# 003_Debugging.net
KiCad netlist of a schematic drawn in Altium Designer
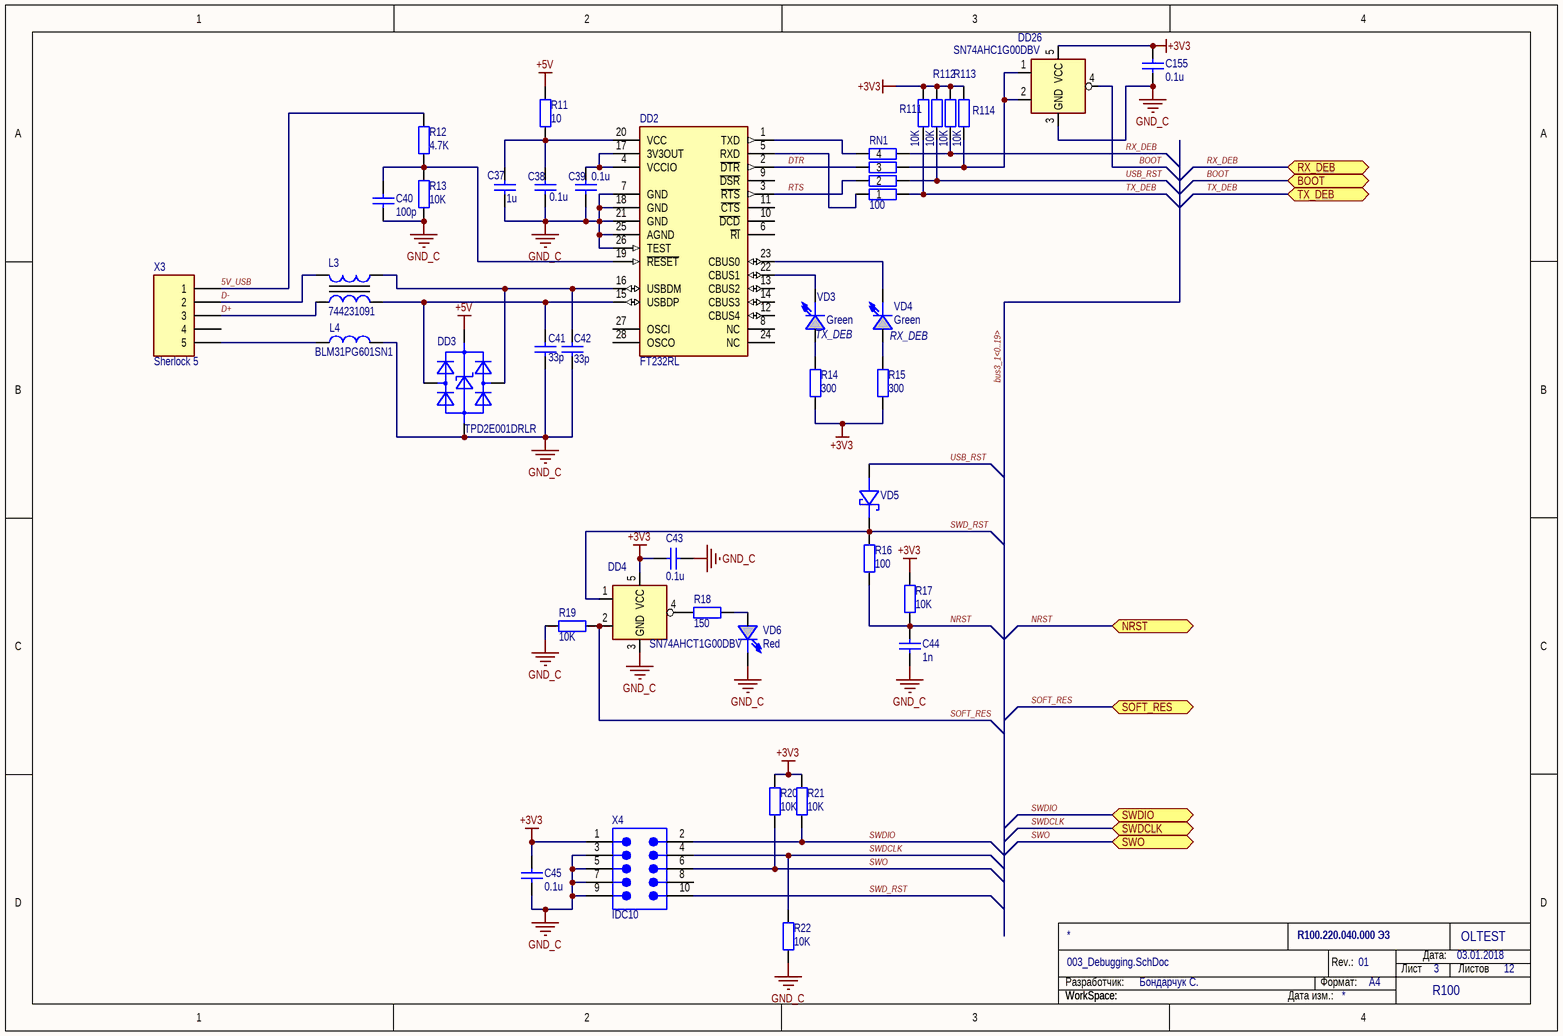
[diagram p0: 003_Debugging.SchDoc]

(export (version "E")
  (design (tool "Eeschema 10.0.6"))
  (components
    (comp (ref "C37")
      (value "1u")
      (footprint "mainLib:SMD_C_0603")
      (description "SMD C 0603 MURATA 25V 10% X7R")
      (fields (field (name "PARTNUMBER") "GRM188R71E105KA12") (field (name "MANUFACTURER") "MURATA"))
      (libsource (lib "mainRCLib") (part "C0603 1uF 25V 10%"))
    )
    (comp (ref "C38")
      (value "0.1u")
      (footprint "mainLib:SMD_C_0603")
      (description "SMD C 0603 MURATA 50V 10% X7R")
      (fields (field (name "PARTNUMBER") "GRM188R71H104K") (field (name "MANUFACTURER") "MURATA"))
      (libsource (lib "mainRCLib") (part "C0603 0.1u 50V 10%"))
    )
    (comp (ref "C39")
      (value "0.1u")
      (footprint "mainLib:SMD_C_0603")
      (description "SMD C 0603 MURATA 50V 10% X7R")
      (fields (field (name "PARTNUMBER") "GRM188R71H104K") (field (name "MANUFACTURER") "MURATA"))
      (libsource (lib "mainRCLib") (part "C0603 0.1u 50V 10%"))
    )
    (comp (ref "C40")
      (value "100p")
      (footprint "mainLib:SMD_C_0603")
      (description "SMD C 0603 MURATA 100V 5% NP0")
      (fields (field (name "PARTNUMBER") "GRM1885C2A101JA01") (field (name "MANUFACTURER") "MURATA"))
      (libsource (lib "mainRCLib") (part "C0603 100p 100V 5%"))
    )
    (comp (ref "C41")
      (value "33p")
      (footprint "mainLib:SMD_C_0603")
      (description "SMD C 0603 MURATA 50V 5% NP0")
      (fields (field (name "PARTNUMBER") "GRM1885C1H330JA01") (field (name "MANUFACTURER") "MURATA"))
      (libsource (lib "mainRCLib") (part "C0603 33p 50V 5%"))
    )
    (comp (ref "C42")
      (value "33p")
      (footprint "mainLib:SMD_C_0603")
      (description "SMD C 0603 MURATA 50V 5% NP0")
      (fields (field (name "PARTNUMBER") "GRM1885C1H330JA01") (field (name "MANUFACTURER") "MURATA"))
      (libsource (lib "mainRCLib") (part "C0603 33p 50V 5%"))
    )
    (comp (ref "C43")
      (value "0.1u")
      (footprint "mainLib:SMD_C_0603")
      (description "SMD C 0603 MURATA 50V 10% X7R")
      (fields (field (name "PARTNUMBER") "GRM188R71H104K") (field (name "MANUFACTURER") "MURATA"))
      (libsource (lib "mainRCLib") (part "C0603 0.1u 50V 10%"))
    )
    (comp (ref "C44")
      (value "1n")
      (footprint "mainLib:SMD_C_0603")
      (description "SMD C 0603 MURATA 50V 5% NP0")
      (fields (field (name "PARTNUMBER") "GRM1885C1H102JA01") (field (name "MANUFACTURER") "MURATA"))
      (libsource (lib "mainRCLib") (part "C0603 1n 50V 5%"))
    )
    (comp (ref "C45")
      (value "0.1u")
      (footprint "mainLib:SMD_C_0603")
      (description "SMD C 0603 MURATA 50V 10% X7R")
      (fields (field (name "PARTNUMBER") "GRM188R71H104K") (field (name "MANUFACTURER") "MURATA"))
      (libsource (lib "mainRCLib") (part "C0603 0.1u 50V 10%"))
    )
    (comp (ref "C155")
      (value "0.1u")
      (footprint "mainLib:SMD_C_0603")
      (description "SMD C 0603 MURATA 50V 10% X7R")
      (fields (field (name "PARTNUMBER") "GRM188R71H104K") (field (name "MANUFACTURER") "MURATA"))
      (libsource (lib "mainRCLib") (part "C0603 0.1u 50V 10%"))
    )
    (comp (ref "DD2")
      (value "FT232RL")
      (footprint "mainLib:SSOP-28_M")
      (description "USB UART Asynchronous Serial Data Transfer Chip, 28-pin SSOP")
      (fields (field (name "MANUFACTURER") "FTDI"))
      (libsource (lib "mainLib") (part "FT232RL"))
    )
    (comp (ref "DD3")
      (value "TPD2E001DRLR")
      (footprint "mainLib:DRL5_M")
      (fields (field (name "MANUFACTURER") "Texas Instruments"))
      (libsource (lib "mainLib") (part "TPD2E001DRLR"))
    )
    (comp (ref "DD4")
      (value "SN74AHCT1G00DBV")
      (footprint "mainLib:SOT-23(DBV)")
      (description "2-in NAND")
      (fields (field (name "MANUFACTURER") "Texas Instruments"))
      (libsource (lib "mainLib") (part "SN74AHCT1G00DBV"))
    )
    (comp (ref "DD26")
      (value "SN74AHC1G00DBV")
      (footprint "mainLib:SOT-23(DBV)")
      (description "2-in NAND")
      (fields (field (name "MANUFACTURER") "Texas Instruments"))
      (libsource (lib "mainLib") (part "SN74AHC1G00DBV"))
    )
    (comp (ref "L3")
      (value "744231091")
      (footprint "mainLib:WE-CNSW-0805")
      (description "SMD Common Mode Noise Suppressor WE-CNSW, Z = 90 Ohm")
      (fields (field (name "MANUFACTURER") "Wurth Elektronik"))
      (libsource (lib "mainLib") (part "744231091"))
    )
    (comp (ref "L4")
      (value "BLM31PG601SN1")
      (footprint "mainLib:SMD_L_1206")
      (description "600R 1.5A (100MHz)")
      (fields (field (name "MANUFACTURER") "TDK") (field (name "PARTNUMBER") "BLM31PG601SN1"))
      (libsource (lib "mainLib") (part "BLM31PG601SN1"))
    )
    (comp (ref "R11")
      (value "10")
      (footprint "mainLib:SMD_R_0805")
      (description "SMD R 0805 VISHAY 0.125W 150V 1% 100ppm")
      (fields (field (name "PARTNUMBER") "CRCW080510R0FK") (field (name "MANUFACTURER") "VISHAY"))
      (libsource (lib "mainRCLib") (part "R0805 10 1%"))
    )
    (comp (ref "R12")
      (value "4.7K")
      (footprint "mainLib:SMD_R_0805")
      (description "SMD R 0805 VISHAY 0.125W 150V 1% 100ppm")
      (fields (field (name "PARTNUMBER") "CRCW08054K70FK") (field (name "MANUFACTURER") "VISHAY"))
      (libsource (lib "mainRCLib") (part "R0805 4.7K 1%"))
    )
    (comp (ref "R13")
      (value "10K")
      (footprint "mainLib:SMD_R_0805")
      (description "SMD R 0805 VISHAY 0.125W 150V 1% 100ppm")
      (fields (field (name "PARTNUMBER") "CRCW080510K0FK") (field (name "MANUFACTURER") "VISHAY"))
      (libsource (lib "mainRCLib") (part "R0805 10K 1%"))
    )
    (comp (ref "R14")
      (value "300")
      (footprint "mainLib:SMD_R_0805")
      (description "SMD R 0805 VISHAY 0.125W 150V 1% 100ppm")
      (fields (field (name "PARTNUMBER") "CRCW0805300RFK") (field (name "MANUFACTURER") "VISHAY"))
      (libsource (lib "mainRCLib") (part "R0805 300 1%"))
    )
    (comp (ref "R15")
      (value "300")
      (footprint "mainLib:SMD_R_0805")
      (description "SMD R 0805 VISHAY 0.125W 150V 1% 100ppm")
      (fields (field (name "PARTNUMBER") "CRCW0805300RFK") (field (name "MANUFACTURER") "VISHAY"))
      (libsource (lib "mainRCLib") (part "R0805 300 1%"))
    )
    (comp (ref "R16")
      (value "100")
      (footprint "SMD_R_0603")
      (description "SMD R 0603 VISHAY 0.1W 75V 1% 100ppm")
      (fields (field (name "PARTNUMBER") "CRCW0603100RFK") (field (name "MANUFACTURER") "VISHAY"))
      (libsource (lib "mainRCLib") (part "R0603 100 1%"))
    )
    (comp (ref "R17")
      (value "10K")
      (footprint "SMD_R_0603")
      (description "SMD R 0603 VISHAY 0.1W 75V 1% 100ppm")
      (fields (field (name "PARTNUMBER") "CRCW060310K0FK") (field (name "MANUFACTURER") "VISHAY"))
      (libsource (lib "mainRCLib") (part "R0603 10К 1%"))
    )
    (comp (ref "R18")
      (value "150")
      (footprint "mainLib:SMD_R_0805")
      (description "SMD 0805 VISHAY 0.125W 150V 1% 100ppm")
      (fields (field (name "PARTNUMBER") "CRCW0805150RFK") (field (name "MANUFACTURER") "VISHAY"))
      (libsource (lib "mainRCLib") (part "R0805 150 1%"))
    )
    (comp (ref "R19")
      (value "10K")
      (footprint "SMD_R_0603")
      (description "SMD R 0603 VISHAY 0.1W 75V 1% 100ppm")
      (fields (field (name "PARTNUMBER") "CRCW060310K0FK") (field (name "MANUFACTURER") "VISHAY"))
      (libsource (lib "") (part "R0603 10К 1%_1"))
    )
    (comp (ref "R20")
      (value "10K")
      (footprint "SMD_R_0603")
      (description "SMD R 0603 VISHAY 0.1W 75V 1% 100ppm")
      (fields (field (name "PARTNUMBER") "CRCW060310K0FK") (field (name "MANUFACTURER") "VISHAY"))
      (libsource (lib "mainRCLib") (part "R0603 10К 1%"))
    )
    (comp (ref "R21")
      (value "10K")
      (footprint "SMD_R_0603")
      (description "SMD R 0603 VISHAY 0.1W 75V 1% 100ppm")
      (fields (field (name "PARTNUMBER") "CRCW060310K0FK") (field (name "MANUFACTURER") "VISHAY"))
      (libsource (lib "mainRCLib") (part "R0603 10К 1%"))
    )
    (comp (ref "R22")
      (value "10K")
      (footprint "SMD_R_0603")
      (description "SMD R 0603 VISHAY 0.1W 75V 1% 100ppm")
      (fields (field (name "PARTNUMBER") "CRCW060310K0FK") (field (name "MANUFACTURER") "VISHAY"))
      (libsource (lib "mainRCLib") (part "R0603 10К 1%"))
    )
    (comp (ref "R111")
      (value "10K")
      (footprint "SMD_R_0603")
      (description "SMD R 0603 VISHAY 0.1W 75V 1% 100ppm")
      (fields (field (name "PARTNUMBER") "CRCW060310K0FK") (field (name "MANUFACTURER") "VISHAY"))
      (libsource (lib "mainRCLib") (part "R0603 10К 1%"))
    )
    (comp (ref "R112")
      (value "10K")
      (footprint "SMD_R_0603")
      (description "SMD R 0603 VISHAY 0.1W 75V 1% 100ppm")
      (fields (field (name "PARTNUMBER") "CRCW060310K0FK") (field (name "MANUFACTURER") "VISHAY"))
      (libsource (lib "mainRCLib") (part "R0603 10К 1%"))
    )
    (comp (ref "R113")
      (value "10K")
      (footprint "SMD_R_0603")
      (description "SMD R 0603 VISHAY 0.1W 75V 1% 100ppm")
      (fields (field (name "PARTNUMBER") "CRCW060310K0FK") (field (name "MANUFACTURER") "VISHAY"))
      (libsource (lib "mainRCLib") (part "R0603 10К 1%"))
    )
    (comp (ref "R114")
      (value "10K")
      (footprint "SMD_R_0603")
      (description "SMD R 0603 VISHAY 0.1W 75V 1% 100ppm")
      (fields (field (name "PARTNUMBER") "CRCW060310K0FK") (field (name "MANUFACTURER") "VISHAY"))
      (libsource (lib "mainRCLib") (part "R0603 10К 1%"))
    )
    (comp (ref "RN1")
      (value "100")
      (footprint "mainLib:CRA06S")
      (description "SMD RESISTOR ARRAY VISHAY 0.063W 50V 1% 100ppm")
      (fields (field (name "PARTNUMBER") "CRA06S083100RF") (field (name "MANUFACTURER") "VISHAY"))
      (libsource (lib "mainRCLib") (part "CRA06S 4x100 1%"))
    )
    (comp (ref "VD3")
      (value "Green")
      (footprint "mainLib:SMD_LED_LL_Green")
      (description "LED Green SMD")
      (fields (field (name "PARTNUMBER") "LL-S172GC-2A") (field (name "MANUFACTURER") "Lucky Light"))
      (libsource (lib "mainLib") (part "LL-S172GC-2A"))
    )
    (comp (ref "VD4")
      (value "Green")
      (footprint "mainLib:SMD_LED_LL_Green")
      (description "LED Green SMD")
      (fields (field (name "PARTNUMBER") "LL-S172GC-2A") (field (name "MANUFACTURER") "Lucky Light"))
      (libsource (lib "mainLib") (part "LL-S172GC-2A"))
    )
    (comp (ref "VD5")
      (value "MBR0540T1G")
      (footprint "mainLib:SOD-123")
      (description "0.5A/40V Schottky Diode (SOD-123)")
      (fields (field (name "MANUFACTURER") "ON Semiconductor"))
      (libsource (lib "mainLib") (part "MBR0540T1G"))
    )
    (comp (ref "VD6")
      (value "Red")
      (footprint "mainLib:SMD_LED_LL_Red")
      (description "LED Red SMD")
      (fields (field (name "PARTNUMBER") "LL-S172SC-2S") (field (name "MANUFACTURER") "Lucky Light"))
      (libsource (lib "mainLib") (part "LL-S172SC-2S"))
    )
    (comp (ref "X3")
      (value "Sherlock 5")
      (footprint "mainLib:35362-0550")
      (description "Sherlock 5 Top, 2A 125V 2mm")
      (fields (field (name "PARTNUMBER") "35362-0550") (field (name "MANUFACTURER") "MOLEX"))
      (libsource (lib "mainLib") (part "35362-0550"))
    )
    (comp (ref "X4")
      (value "IDC10")
      (footprint "mainLib:918510x324")
      (fields (field (name "PARTNUMBER") "09 18 510 6904") (field (name "PUBLISHER") "Altium Limited"))
      (libsource (lib "mainLib") (part "Harting IDC10 904"))
    )
  )
  (nets
    (net (code "2") (name "+3V3") (class "Default")
      (node (ref "C155") (pin "1") (pinfunction "1_1") (pintype "passive"))
      (node (ref "C43") (pin "2") (pinfunction "2_2") (pintype "passive"))
      (node (ref "C45") (pin "2") (pinfunction "2_2") (pintype "passive"))
      (node (ref "DD26") (pin "5") (pinfunction "VCC_5") (pintype "passive"))
      (node (ref "DD4") (pin "5") (pinfunction "VCC_5") (pintype "passive"))
      (node (ref "R111") (pin "2") (pinfunction "2_2") (pintype "passive"))
      (node (ref "R112") (pin "2") (pinfunction "2_2") (pintype "passive"))
      (node (ref "R113") (pin "2") (pinfunction "2_2") (pintype "passive"))
      (node (ref "R114") (pin "2") (pinfunction "2_2") (pintype "passive"))
      (node (ref "R14") (pin "1") (pinfunction "1_1") (pintype "passive"))
      (node (ref "R15") (pin "1") (pinfunction "1_1") (pintype "passive"))
      (node (ref "R17") (pin "2") (pinfunction "2_2") (pintype "passive"))
      (node (ref "R20") (pin "2") (pinfunction "2_2") (pintype "passive"))
      (node (ref "R21") (pin "2") (pinfunction "2_2") (pintype "passive"))
      (node (ref "X4") (pin "1") (pinfunction "1_1") (pintype "passive"))
    )
    (net (code "3") (name "+5V") (class "Default")
      (node (ref "DD3") (pin "1") (pinfunction "VCC_1") (pintype "power_in"))
      (node (ref "R11") (pin "2") (pinfunction "2_2") (pintype "passive"))
    )
    (net (code "4") (name "/5V_USB") (class "Default")
      (node (ref "R12") (pin "2") (pinfunction "2_2") (pintype "passive"))
      (node (ref "X3") (pin "1") (pinfunction "1_1") (pintype "passive"))
    )
    (net (code "5") (name "/BOOT") (class "Default") (node (ref "DD26") (pin "4") (pintype "passive")))
    (net (code "6") (name "/D+") (class "Default")
      (node (ref "L3") (pin "1") (pinfunction "1_1") (pintype "passive"))
      (node (ref "X3") (pin "3") (pinfunction "3_3") (pintype "passive"))
    )
    (net (code "7") (name "/D-") (class "Default")
      (node (ref "L3") (pin "4") (pinfunction "4_4") (pintype "passive"))
      (node (ref "X3") (pin "2") (pinfunction "2_2") (pintype "passive"))
    )
    (net (code "8") (name "/DTR") (class "Default")
      (node (ref "DD2") (pin "2") (pinfunction "~{DTR}_2") (pintype "output"))
      (node (ref "RN1") (pin "3") (pinfunction "3_3") (pintype "passive"))
    )
    (net (code "9") (name "/NRST") (class "Default")
      (node (ref "C44") (pin "2") (pinfunction "2_2") (pintype "passive"))
      (node (ref "R16") (pin "1") (pinfunction "1_1") (pintype "passive"))
      (node (ref "R17") (pin "1") (pinfunction "1_1") (pintype "passive"))
    )
    (net (code "10") (name "/RTS") (class "Default")
      (node (ref "DD2") (pin "3") (pinfunction "~{RTS}_3") (pintype "output"))
      (node (ref "RN1") (pin "2") (pinfunction "2_2") (pintype "passive"))
    )
    (net (code "11") (name "/RX_DEB") (class "Default")
      (node (ref "R113") (pin "1") (pinfunction "1_1") (pintype "passive"))
      (node (ref "RN1") (pin "5") (pinfunction "5_5") (pintype "passive"))
    )
    (net (code "12") (name "/SOFT_RES") (class "Default")
      (node (ref "DD4") (pin "2") (pintype "passive"))
      (node (ref "R19") (pin "1") (pinfunction "1_1") (pintype "passive"))
    )
    (net (code "13") (name "/SWDCLK") (class "Default")
      (node (ref "R22") (pin "2") (pinfunction "2_2") (pintype "passive"))
      (node (ref "X4") (pin "4") (pinfunction "4_4") (pintype "passive"))
    )
    (net (code "14") (name "/SWDIO") (class "Default")
      (node (ref "R21") (pin "1") (pinfunction "1_1") (pintype "passive"))
      (node (ref "X4") (pin "2") (pinfunction "2_2") (pintype "passive"))
    )
    (net (code "15") (name "/SWD_RST") (class "Default")
      (node (ref "DD4") (pin "1") (pintype "passive"))
      (node (ref "R16") (pin "2") (pinfunction "2_2") (pintype "passive"))
      (node (ref "VD5") (pin "1") (pinfunction "Cathode_1") (pintype "passive"))
      (node (ref "X4") (pin "10") (pinfunction "10_10") (pintype "passive"))
    )
    (net (code "16") (name "/SWO") (class "Default")
      (node (ref "R20") (pin "1") (pinfunction "1_1") (pintype "passive"))
      (node (ref "X4") (pin "6") (pinfunction "6_6") (pintype "passive"))
    )
    (net (code "17") (name "/TX_DEB") (class "Default")
      (node (ref "R111") (pin "1") (pinfunction "1_1") (pintype "passive"))
      (node (ref "RN1") (pin "8") (pinfunction "8_8") (pintype "passive"))
    )
    (net (code "18") (name "/USB_RST") (class "Default")
      (node (ref "R112") (pin "1") (pinfunction "1_1") (pintype "passive"))
      (node (ref "RN1") (pin "7") (pinfunction "7_7") (pintype "passive"))
      (node (ref "VD5") (pin "2") (pinfunction "Anode_2") (pintype "passive"))
    )
    (net (code "20") (name "GND_C") (class "Default")
      (node (ref "C155") (pin "2") (pinfunction "2_2") (pintype "passive"))
      (node (ref "C37") (pin "1") (pinfunction "1_1") (pintype "passive"))
      (node (ref "C38") (pin "1") (pinfunction "1_1") (pintype "passive"))
      (node (ref "C39") (pin "1") (pinfunction "1_1") (pintype "passive"))
      (node (ref "C40") (pin "1") (pinfunction "1_1") (pintype "passive"))
      (node (ref "C41") (pin "2") (pinfunction "2_2") (pintype "passive"))
      (node (ref "C42") (pin "2") (pinfunction "2_2") (pintype "passive"))
      (node (ref "C43") (pin "1") (pinfunction "1_1") (pintype "passive"))
      (node (ref "C44") (pin "1") (pinfunction "1_1") (pintype "passive"))
      (node (ref "C45") (pin "1") (pinfunction "1_1") (pintype "passive"))
      (node (ref "DD2") (pin "18") (pinfunction "GND_18") (pintype "power_in"))
      (node (ref "DD2") (pin "21") (pinfunction "GND_21") (pintype "power_in"))
      (node (ref "DD2") (pin "25") (pinfunction "AGND_25") (pintype "power_in"))
      (node (ref "DD2") (pin "26") (pinfunction "TEST_26") (pintype "input"))
      (node (ref "DD2") (pin "7") (pinfunction "GND_7") (pintype "power_in"))
      (node (ref "DD26") (pin "3") (pinfunction "GND_3") (pintype "passive"))
      (node (ref "DD3") (pin "4") (pinfunction "GND_4") (pintype "power_in"))
      (node (ref "DD4") (pin "3") (pinfunction "GND_3") (pintype "passive"))
      (node (ref "L4") (pin "2") (pinfunction "2_2") (pintype "passive"))
      (node (ref "R13") (pin "1") (pinfunction "1_1") (pintype "passive"))
      (node (ref "R19") (pin "2") (pinfunction "2_2") (pintype "passive"))
      (node (ref "R22") (pin "1") (pinfunction "1_1") (pintype "passive"))
      (node (ref "VD6") (pin "2") (pinfunction "CATHODE_2") (pintype "passive"))
      (node (ref "X4") (pin "3") (pinfunction "3_3") (pintype "passive"))
      (node (ref "X4") (pin "5") (pinfunction "5_5") (pintype "passive"))
      (node (ref "X4") (pin "7") (pinfunction "7_7") (pintype "passive"))
      (node (ref "X4") (pin "9") (pinfunction "9_9") (pintype "passive"))
    )
    (net (code "21") (name "Net-(DD2-3V3OUT)") (class "Default")
      (node (ref "C39") (pin "2") (pinfunction "2_2") (pintype "passive"))
      (node (ref "DD2") (pin "17") (pinfunction "3V3OUT_17") (pintype "passive"))
      (node (ref "DD2") (pin "4") (pinfunction "VCCIO_4") (pintype "power_in"))
    )
    (net (code "22") (name "Net-(DD2-CBUS0)") (class "Default")
      (node (ref "DD2") (pin "23") (pinfunction "CBUS0_23") (pintype "bidirectional"))
      (node (ref "VD4") (pin "2") (pinfunction "CATHODE_2") (pintype "passive"))
    )
    (net (code "23") (name "Net-(DD2-CBUS1)") (class "Default")
      (node (ref "DD2") (pin "22") (pinfunction "CBUS1_22") (pintype "bidirectional"))
      (node (ref "VD3") (pin "2") (pinfunction "CATHODE_2") (pintype "passive"))
    )
    (net (code "24") (name "Net-(DD2-RXD)") (class "Default")
      (node (ref "DD2") (pin "5") (pinfunction "RXD_5") (pintype "passive"))
      (node (ref "RN1") (pin "1") (pinfunction "1_1") (pintype "passive"))
    )
    (net (code "25") (name "Net-(DD2-TXD)") (class "Default")
      (node (ref "DD2") (pin "1") (pinfunction "TXD_1") (pintype "output"))
      (node (ref "RN1") (pin "4") (pinfunction "4_4") (pintype "passive"))
    )
    (net (code "26") (name "Net-(DD2-USBDM)") (class "Default")
      (node (ref "C42") (pin "1") (pinfunction "1_1") (pintype "passive"))
      (node (ref "DD2") (pin "16") (pinfunction "USBDM_16") (pintype "bidirectional"))
      (node (ref "DD3") (pin "5") (pinfunction "IO2_5") (pintype "passive"))
      (node (ref "L3") (pin "3") (pinfunction "3_3") (pintype "passive"))
    )
    (net (code "27") (name "Net-(DD2-USBDP)") (class "Default")
      (node (ref "C41") (pin "1") (pinfunction "1_1") (pintype "passive"))
      (node (ref "DD2") (pin "15") (pinfunction "USBDP_15") (pintype "bidirectional"))
      (node (ref "DD3") (pin "3") (pinfunction "IO1_3") (pintype "passive"))
      (node (ref "L3") (pin "2") (pinfunction "2_2") (pintype "passive"))
    )
    (net (code "28") (name "Net-(DD2-VCC)") (class "Default")
      (node (ref "C37") (pin "2") (pinfunction "2_2") (pintype "passive"))
      (node (ref "C38") (pin "2") (pinfunction "2_2") (pintype "passive"))
      (node (ref "DD2") (pin "20") (pinfunction "VCC_20") (pintype "power_in"))
      (node (ref "R11") (pin "1") (pinfunction "1_1") (pintype "passive"))
    )
    (net (code "29") (name "Net-(DD2-~{RESET})") (class "Default")
      (node (ref "C40") (pin "2") (pinfunction "2_2") (pintype "passive"))
      (node (ref "DD2") (pin "19") (pinfunction "~{RESET}_19") (pintype "input"))
      (node (ref "R12") (pin "1") (pinfunction "1_1") (pintype "passive"))
      (node (ref "R13") (pin "2") (pinfunction "2_2") (pintype "passive"))
    )
    (net (code "30") (name "Net-(DD4-Pad4)") (class "Default")
      (node (ref "DD4") (pin "4") (pintype "passive"))
      (node (ref "R18") (pin "1") (pinfunction "1_1") (pintype "passive"))
    )
    (net (code "31") (name "Net-(DD26-Pad1)") (class "Default")
      (node (ref "DD26") (pin "1") (pintype "passive"))
      (node (ref "DD26") (pin "2") (pintype "passive"))
      (node (ref "R114") (pin "1") (pinfunction "1_1") (pintype "passive"))
      (node (ref "RN1") (pin "6") (pinfunction "6_6") (pintype "passive"))
    )
    (net (code "32") (name "Net-(L4-Pad1)") (class "Default")
      (node (ref "L4") (pin "1") (pinfunction "1_1") (pintype "passive"))
      (node (ref "X3") (pin "5") (pinfunction "5_5") (pintype "passive"))
    )
    (net (code "33") (name "Net-(VD3-ANODE)") (class "Default")
      (node (ref "R14") (pin "2") (pinfunction "2_2") (pintype "passive"))
      (node (ref "VD3") (pin "1") (pinfunction "ANODE_1") (pintype "passive"))
    )
    (net (code "34") (name "Net-(VD4-ANODE)") (class "Default")
      (node (ref "R15") (pin "2") (pinfunction "2_2") (pintype "passive"))
      (node (ref "VD4") (pin "1") (pinfunction "ANODE_1") (pintype "passive"))
    )
    (net (code "35") (name "Net-(VD6-ANODE)") (class "Default")
      (node (ref "R18") (pin "2") (pinfunction "2_2") (pintype "passive"))
      (node (ref "VD6") (pin "1") (pinfunction "ANODE_1") (pintype "passive"))
    )
    (net (code "36") (name "unconnected-(DD2-CBUS2-Pad13)") (class "Default")
      (node (ref "DD2") (pin "13") (pinfunction "CBUS2_13") (pintype "bidirectional"))
    )
    (net (code "37") (name "unconnected-(DD2-CBUS3-Pad14)") (class "Default")
      (node (ref "DD2") (pin "14") (pinfunction "CBUS3_14") (pintype "bidirectional"))
    )
    (net (code "38") (name "unconnected-(DD2-CBUS4-Pad12)") (class "Default")
      (node (ref "DD2") (pin "12") (pinfunction "CBUS4_12") (pintype "bidirectional"))
    )
    (net (code "39") (name "unconnected-(DD2-NC-Pad8)") (class "Default")
      (node (ref "DD2") (pin "8") (pinfunction "NC_8") (pintype "passive"))
    )
    (net (code "40") (name "unconnected-(DD2-NC-Pad24)") (class "Default")
      (node (ref "DD2") (pin "24") (pinfunction "NC_24") (pintype "passive"))
    )
    (net (code "41") (name "unconnected-(DD2-OSCI-Pad27)") (class "Default")
      (node (ref "DD2") (pin "27") (pinfunction "OSCI_27") (pintype "passive"))
    )
    (net (code "42") (name "unconnected-(DD2-OSCO-Pad28)") (class "Default")
      (node (ref "DD2") (pin "28") (pinfunction "OSCO_28") (pintype "passive"))
    )
    (net (code "43") (name "unconnected-(DD2-~{CTS}-Pad11)") (class "Default")
      (node (ref "DD2") (pin "11") (pinfunction "~{CTS}_11") (pintype "passive"))
    )
    (net (code "44") (name "unconnected-(DD2-~{DCD}-Pad10)") (class "Default")
      (node (ref "DD2") (pin "10") (pinfunction "~{DCD}_10") (pintype "passive"))
    )
    (net (code "45") (name "unconnected-(DD2-~{DSR}-Pad9)") (class "Default")
      (node (ref "DD2") (pin "9") (pinfunction "~{DSR}_9") (pintype "passive"))
    )
    (net (code "46") (name "unconnected-(DD2-~{RI}-Pad6)") (class "Default")
      (node (ref "DD2") (pin "6") (pinfunction "~{RI}_6") (pintype "passive"))
    )
    (net (code "47") (name "unconnected-(X3-Pad4)") (class "Default")
      (node (ref "X3") (pin "4") (pinfunction "4_4") (pintype "passive"))
    )
    (net (code "48") (name "unconnected-(X4-Pad8)") (class "Default")
      (node (ref "X4") (pin "8") (pinfunction "8_8") (pintype "passive"))
    )
  )
)
